# Vertical_Breakout_Module.net
KiCad netlist of a schematic drawn in EAGLE
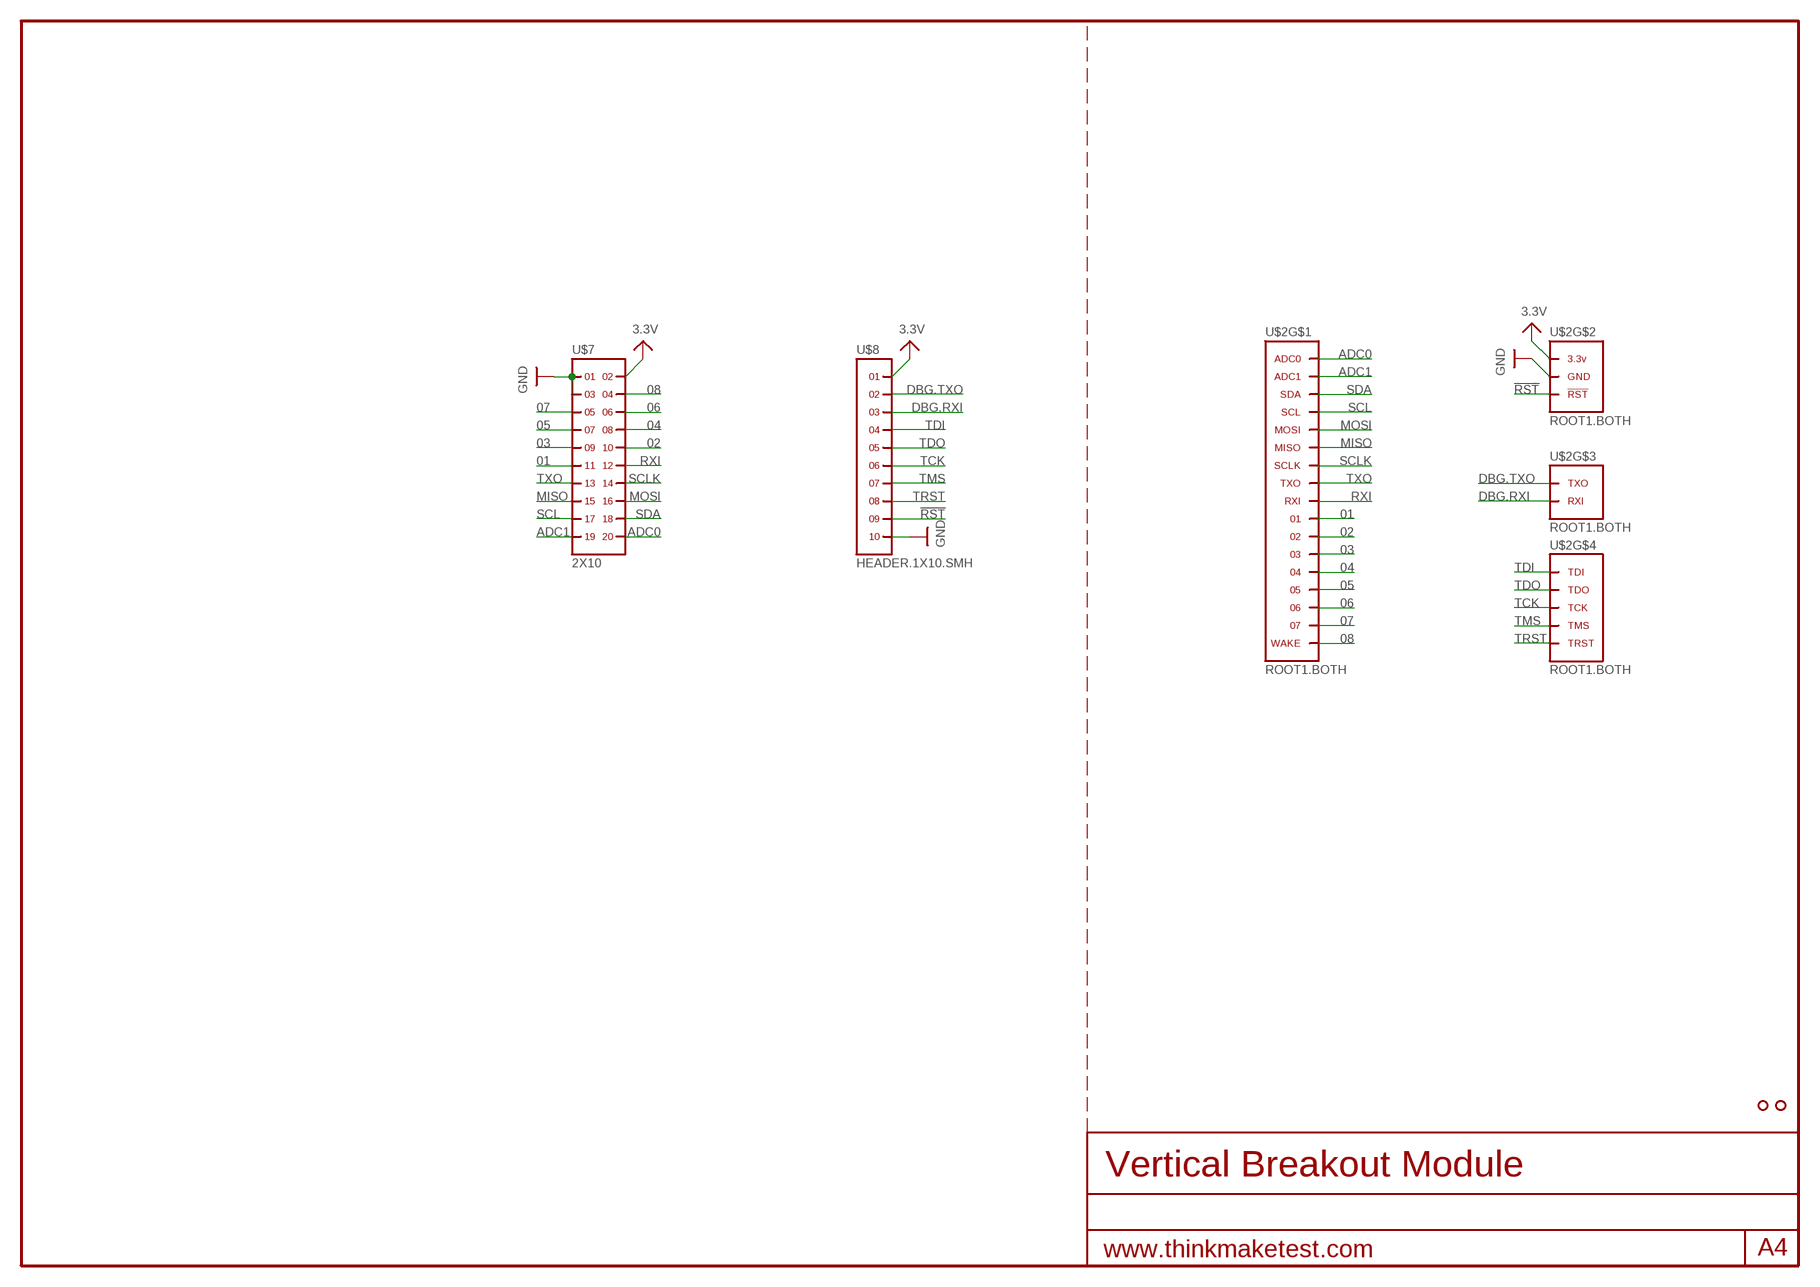
[diagram p0: schematic, sheet 1]

(export (version "E")
  (design (tool "Eeschema 10.0.6"))
  (components
    (comp (ref "U$2")
      (value "ROOT1.BOTH")
      (footprint "eagle-import:ROOT1.BOTH")
      (libsource (lib "eagle-import") (part "ROOT1.BOTH"))
    )
    (comp (ref "U$3")
      (value "HOLE.#2")
      (footprint "eagle-import:#2")
      (libsource (lib "eagle-import") (part "HOLE.#2"))
    )
    (comp (ref "U$4")
      (value "HOLE.#2")
      (footprint "eagle-import:#2")
      (libsource (lib "eagle-import") (part "HOLE.#2"))
    )
    (comp (ref "U$7")
      (value "2X10")
      (footprint "eagle-import:2X10")
      (libsource (lib "eagle-import") (part "2X10"))
    )
    (comp (ref "U$8")
      (value "HEADER.1X10.SMH")
      (footprint "eagle-import:SMH-110-XX-X-S")
      (libsource (lib "eagle-import") (part "HEADER.1X10.SMH"))
    )
  )
  (nets
    (net (code "1") (name "/01") (class "Default")
      (node (ref "U$2") (pin "01") (pinfunction "01_01") (pintype "bidirectional"))
      (node (ref "U$2") (pin "01@1") (pinfunction "01_01@1") (pintype "bidirectional"))
      (node (ref "U$2") (pin "01@VIA") (pinfunction "01_01@VIA") (pintype "bidirectional"))
      (node (ref "U$7") (pin "11") (pinfunction "11_11") (pintype "bidirectional"))
    )
    (net (code "2") (name "/02") (class "Default")
      (node (ref "U$2") (pin "02") (pinfunction "02_02") (pintype "bidirectional"))
      (node (ref "U$2") (pin "02@1") (pinfunction "02_02@1") (pintype "bidirectional"))
      (node (ref "U$2") (pin "02@VIA") (pinfunction "02_02@VIA") (pintype "bidirectional"))
      (node (ref "U$7") (pin "10") (pinfunction "10_10") (pintype "bidirectional"))
    )
    (net (code "3") (name "/03") (class "Default")
      (node (ref "U$2") (pin "03") (pinfunction "03_03") (pintype "bidirectional"))
      (node (ref "U$2") (pin "03@1") (pinfunction "03_03@1") (pintype "bidirectional"))
      (node (ref "U$2") (pin "03@VIA") (pinfunction "03_03@VIA") (pintype "bidirectional"))
      (node (ref "U$7") (pin "9") (pinfunction "9_9") (pintype "bidirectional"))
    )
    (net (code "4") (name "/04") (class "Default")
      (node (ref "U$2") (pin "04") (pinfunction "04_04") (pintype "bidirectional"))
      (node (ref "U$2") (pin "04@1") (pinfunction "04_04@1") (pintype "bidirectional"))
      (node (ref "U$2") (pin "04@VIA") (pinfunction "04_04@VIA") (pintype "bidirectional"))
      (node (ref "U$7") (pin "8") (pinfunction "8_8") (pintype "bidirectional"))
    )
    (net (code "5") (name "/05") (class "Default")
      (node (ref "U$2") (pin "05") (pinfunction "05_05") (pintype "bidirectional"))
      (node (ref "U$2") (pin "05@1") (pinfunction "05_05@1") (pintype "bidirectional"))
      (node (ref "U$2") (pin "05@VIA") (pinfunction "05_05@VIA") (pintype "bidirectional"))
      (node (ref "U$7") (pin "7") (pinfunction "7_7") (pintype "bidirectional"))
    )
    (net (code "6") (name "/06") (class "Default")
      (node (ref "U$2") (pin "06") (pinfunction "06_06") (pintype "bidirectional"))
      (node (ref "U$2") (pin "06@1") (pinfunction "06_06@1") (pintype "bidirectional"))
      (node (ref "U$2") (pin "06@VIA") (pinfunction "06_06@VIA") (pintype "bidirectional"))
      (node (ref "U$7") (pin "6") (pinfunction "6_6") (pintype "bidirectional"))
    )
    (net (code "7") (name "/07") (class "Default")
      (node (ref "U$2") (pin "07") (pinfunction "07_07") (pintype "bidirectional"))
      (node (ref "U$2") (pin "07@1") (pinfunction "07_07@1") (pintype "bidirectional"))
      (node (ref "U$2") (pin "07@VIA") (pinfunction "07_07@VIA") (pintype "bidirectional"))
      (node (ref "U$7") (pin "5") (pinfunction "5_5") (pintype "bidirectional"))
    )
    (net (code "8") (name "/08") (class "Default")
      (node (ref "U$2") (pin "WAKE") (pinfunction "WAKE_WAKE") (pintype "bidirectional"))
      (node (ref "U$2") (pin "WAKE@1") (pinfunction "WAKE_WAKE@1") (pintype "bidirectional"))
      (node (ref "U$2") (pin "WAKE@VIA") (pinfunction "WAKE_WAKE@VIA") (pintype "bidirectional"))
      (node (ref "U$7") (pin "4") (pinfunction "4_4") (pintype "bidirectional"))
    )
    (net (code "9") (name "/ADC0") (class "Default")
      (node (ref "U$2") (pin "ADC0") (pinfunction "ADC0_ADC0") (pintype "bidirectional"))
      (node (ref "U$2") (pin "ADC0@1") (pinfunction "ADC0_ADC0@1") (pintype "bidirectional"))
      (node (ref "U$2") (pin "ADC0@VIA") (pinfunction "ADC0_ADC0@VIA") (pintype "bidirectional"))
      (node (ref "U$7") (pin "20") (pinfunction "20_20") (pintype "bidirectional"))
    )
    (net (code "10") (name "/ADC1") (class "Default")
      (node (ref "U$2") (pin "ADC1") (pinfunction "ADC1_ADC1") (pintype "bidirectional"))
      (node (ref "U$2") (pin "ADC1@1") (pinfunction "ADC1_ADC1@1") (pintype "bidirectional"))
      (node (ref "U$2") (pin "ADC1@VIA") (pinfunction "ADC1_ADC1@VIA") (pintype "bidirectional"))
      (node (ref "U$7") (pin "19") (pinfunction "19_19") (pintype "bidirectional"))
    )
    (net (code "11") (name "/DBG.RXI") (class "Default")
      (node (ref "U$2") (pin "RXI.DBG") (pinfunction "RXI_RXI.DBG") (pintype "bidirectional"))
      (node (ref "U$2") (pin "RXI.DBG@1") (pinfunction "RXI_RXI.DBG@1") (pintype "bidirectional"))
      (node (ref "U$2") (pin "RXI.DBG@VIA") (pinfunction "RXI_RXI.DBG@VIA") (pintype "bidirectional"))
      (node (ref "U$8") (pin "3") (pinfunction "3_3") (pintype "bidirectional"))
    )
    (net (code "12") (name "/DBG.TXO") (class "Default")
      (node (ref "U$2") (pin "TXO.DBG") (pinfunction "TXO_TXO.DBG") (pintype "bidirectional"))
      (node (ref "U$2") (pin "TXO.DBG@1") (pinfunction "TXO_TXO.DBG@1") (pintype "bidirectional"))
      (node (ref "U$2") (pin "TXO.DBG@VIA") (pinfunction "TXO_TXO.DBG@VIA") (pintype "bidirectional"))
      (node (ref "U$8") (pin "2") (pinfunction "2_2") (pintype "bidirectional"))
    )
    (net (code "13") (name "/MISO") (class "Default")
      (node (ref "U$2") (pin "MISO") (pinfunction "MISO_MISO") (pintype "bidirectional"))
      (node (ref "U$2") (pin "MISO@1") (pinfunction "MISO_MISO@1") (pintype "bidirectional"))
      (node (ref "U$2") (pin "MISO@VIA") (pinfunction "MISO_MISO@VIA") (pintype "bidirectional"))
      (node (ref "U$7") (pin "15") (pinfunction "15_15") (pintype "bidirectional"))
    )
    (net (code "14") (name "/MOSI") (class "Default")
      (node (ref "U$2") (pin "MOSI") (pinfunction "MOSI_MOSI") (pintype "bidirectional"))
      (node (ref "U$2") (pin "MOSI@1") (pinfunction "MOSI_MOSI@1") (pintype "bidirectional"))
      (node (ref "U$2") (pin "MOSI@VIA") (pinfunction "MOSI_MOSI@VIA") (pintype "bidirectional"))
      (node (ref "U$7") (pin "16") (pinfunction "16_16") (pintype "bidirectional"))
    )
    (net (code "15") (name "/RXI") (class "Default")
      (node (ref "U$2") (pin "RXI") (pinfunction "RXI_RXI") (pintype "bidirectional"))
      (node (ref "U$2") (pin "RXI@1") (pinfunction "RXI_RXI@1") (pintype "bidirectional"))
      (node (ref "U$2") (pin "RXI@VIA") (pinfunction "RXI_RXI@VIA") (pintype "bidirectional"))
      (node (ref "U$7") (pin "12") (pinfunction "12_12") (pintype "bidirectional"))
    )
    (net (code "16") (name "/SCL") (class "Default")
      (node (ref "U$2") (pin "SCL") (pinfunction "SCL_SCL") (pintype "bidirectional"))
      (node (ref "U$2") (pin "SCL@1") (pinfunction "SCL_SCL@1") (pintype "bidirectional"))
      (node (ref "U$2") (pin "SCL@VIA") (pinfunction "SCL_SCL@VIA") (pintype "bidirectional"))
      (node (ref "U$7") (pin "17") (pinfunction "17_17") (pintype "bidirectional"))
    )
    (net (code "17") (name "/SCLK") (class "Default")
      (node (ref "U$2") (pin "SCLK") (pinfunction "SCLK_SCLK") (pintype "bidirectional"))
      (node (ref "U$2") (pin "SCLK@1") (pinfunction "SCLK_SCLK@1") (pintype "bidirectional"))
      (node (ref "U$2") (pin "SCLK@VIA") (pinfunction "SCLK_SCLK@VIA") (pintype "bidirectional"))
      (node (ref "U$7") (pin "14") (pinfunction "14_14") (pintype "bidirectional"))
    )
    (net (code "18") (name "/SDA") (class "Default")
      (node (ref "U$2") (pin "SDA") (pinfunction "SDA_SDA") (pintype "bidirectional"))
      (node (ref "U$2") (pin "SDA@1") (pinfunction "SDA_SDA@1") (pintype "bidirectional"))
      (node (ref "U$2") (pin "SDA@VIA") (pinfunction "SDA_SDA@VIA") (pintype "bidirectional"))
      (node (ref "U$7") (pin "18") (pinfunction "18_18") (pintype "bidirectional"))
    )
    (net (code "19") (name "/TCK") (class "Default")
      (node (ref "U$2") (pin "TCK") (pinfunction "TCK_TCK") (pintype "bidirectional"))
      (node (ref "U$2") (pin "TCK@1") (pinfunction "TCK_TCK@1") (pintype "bidirectional"))
      (node (ref "U$2") (pin "TCK@VIA") (pinfunction "TCK_TCK@VIA") (pintype "bidirectional"))
      (node (ref "U$8") (pin "6") (pinfunction "6_6") (pintype "bidirectional"))
    )
    (net (code "20") (name "/TDI") (class "Default")
      (node (ref "U$2") (pin "TDI") (pinfunction "TDI_TDI") (pintype "bidirectional"))
      (node (ref "U$2") (pin "TDI@1") (pinfunction "TDI_TDI@1") (pintype "bidirectional"))
      (node (ref "U$2") (pin "TDI@VIA") (pinfunction "TDI_TDI@VIA") (pintype "bidirectional"))
      (node (ref "U$8") (pin "4") (pinfunction "4_4") (pintype "bidirectional"))
    )
    (net (code "21") (name "/TDO") (class "Default")
      (node (ref "U$2") (pin "TDO") (pinfunction "TDO_TDO") (pintype "bidirectional"))
      (node (ref "U$2") (pin "TDO@1") (pinfunction "TDO_TDO@1") (pintype "bidirectional"))
      (node (ref "U$2") (pin "TDO@VIA") (pinfunction "TDO_TDO@VIA") (pintype "bidirectional"))
      (node (ref "U$8") (pin "5") (pinfunction "5_5") (pintype "bidirectional"))
    )
    (net (code "22") (name "/TMS") (class "Default")
      (node (ref "U$2") (pin "TMS") (pinfunction "TMS_TMS") (pintype "bidirectional"))
      (node (ref "U$2") (pin "TMS@1") (pinfunction "TMS_TMS@1") (pintype "bidirectional"))
      (node (ref "U$2") (pin "TMS@VIA") (pinfunction "TMS_TMS@VIA") (pintype "bidirectional"))
      (node (ref "U$8") (pin "7") (pinfunction "7_7") (pintype "bidirectional"))
    )
    (net (code "23") (name "/TRST") (class "Default")
      (node (ref "U$2") (pin "TRST") (pinfunction "TRST_TRST") (pintype "bidirectional"))
      (node (ref "U$2") (pin "TRST@1") (pinfunction "TRST_TRST@1") (pintype "bidirectional"))
      (node (ref "U$2") (pin "TRST@VIA") (pinfunction "TRST_TRST@VIA") (pintype "bidirectional"))
      (node (ref "U$8") (pin "8") (pinfunction "8_8") (pintype "bidirectional"))
    )
    (net (code "24") (name "/TXO") (class "Default")
      (node (ref "U$2") (pin "TXO") (pinfunction "TXO_TXO") (pintype "bidirectional"))
      (node (ref "U$2") (pin "TXO@1") (pinfunction "TXO_TXO@1") (pintype "bidirectional"))
      (node (ref "U$2") (pin "TXO@VIA") (pinfunction "TXO_TXO@VIA") (pintype "bidirectional"))
      (node (ref "U$7") (pin "13") (pinfunction "13_13") (pintype "bidirectional"))
    )
    (net (code "25") (name "/~{RST}") (class "Default")
      (node (ref "U$2") (pin "RST") (pinfunction "~{RST}_RST") (pintype "bidirectional"))
      (node (ref "U$2") (pin "RST@1") (pinfunction "~{RST}_RST@1") (pintype "bidirectional"))
      (node (ref "U$2") (pin "RST@VIA") (pinfunction "~{RST}_RST@VIA") (pintype "bidirectional"))
      (node (ref "U$8") (pin "9") (pinfunction "9_9") (pintype "bidirectional"))
    )
    (net (code "26") (name "3.3V") (class "Default")
      (node (ref "U$2") (pin "3.3V@1") (pinfunction "3.3V_3.3V@1") (pintype "bidirectional"))
      (node (ref "U$2") (pin "3.3V@10") (pinfunction "3.3V_3.3V@10") (pintype "bidirectional"))
      (node (ref "U$2") (pin "3.3V@11") (pinfunction "3.3V_3.3V@11") (pintype "bidirectional"))
      (node (ref "U$2") (pin "3.3V@12") (pinfunction "3.3V_3.3V@12") (pintype "bidirectional"))
      (node (ref "U$2") (pin "3.3V@13") (pinfunction "3.3V_3.3V@13") (pintype "bidirectional"))
      (node (ref "U$2") (pin "3.3V@14") (pinfunction "3.3V_3.3V@14") (pintype "bidirectional"))
      (node (ref "U$2") (pin "3.3V@15") (pinfunction "3.3V_3.3V@15") (pintype "bidirectional"))
      (node (ref "U$2") (pin "3.3V@16") (pinfunction "3.3V_3.3V@16") (pintype "bidirectional"))
      (node (ref "U$2") (pin "3.3V@17") (pinfunction "3.3V_3.3V@17") (pintype "bidirectional"))
      (node (ref "U$2") (pin "3.3V@18") (pinfunction "3.3V_3.3V@18") (pintype "bidirectional"))
      (node (ref "U$2") (pin "3.3V@19") (pinfunction "3.3V_3.3V@19") (pintype "bidirectional"))
      (node (ref "U$2") (pin "3.3V@2") (pinfunction "3.3V_3.3V@2") (pintype "bidirectional"))
      (node (ref "U$2") (pin "3.3V@20") (pinfunction "3.3V_3.3V@20") (pintype "bidirectional"))
      (node (ref "U$2") (pin "3.3V@21") (pinfunction "3.3V_3.3V@21") (pintype "bidirectional"))
      (node (ref "U$2") (pin "3.3V@22") (pinfunction "3.3V_3.3V@22") (pintype "bidirectional"))
      (node (ref "U$2") (pin "3.3V@23") (pinfunction "3.3V_3.3V@23") (pintype "bidirectional"))
      (node (ref "U$2") (pin "3.3V@24") (pinfunction "3.3V_3.3V@24") (pintype "bidirectional"))
      (node (ref "U$2") (pin "3.3V@3") (pinfunction "3.3V_3.3V@3") (pintype "bidirectional"))
      (node (ref "U$2") (pin "3.3V@4") (pinfunction "3.3V_3.3V@4") (pintype "bidirectional"))
      (node (ref "U$2") (pin "3.3V@5") (pinfunction "3.3V_3.3V@5") (pintype "bidirectional"))
      (node (ref "U$2") (pin "3.3V@6") (pinfunction "3.3V_3.3V@6") (pintype "bidirectional"))
      (node (ref "U$2") (pin "3.3V@7") (pinfunction "3.3V_3.3V@7") (pintype "bidirectional"))
      (node (ref "U$2") (pin "3.3V@8") (pinfunction "3.3V_3.3V@8") (pintype "bidirectional"))
      (node (ref "U$2") (pin "3.3V@9") (pinfunction "3.3V_3.3V@9") (pintype "bidirectional"))
      (node (ref "U$2") (pin "3.3V@VIA") (pinfunction "3.3V_3.3V@VIA") (pintype "bidirectional"))
      (node (ref "U$7") (pin "2") (pinfunction "2_2") (pintype "bidirectional"))
      (node (ref "U$8") (pin "1") (pinfunction "1_1") (pintype "bidirectional"))
    )
    (net (code "27") (name "GND") (class "Default")
      (node (ref "U$2") (pin "GND@1") (pinfunction "GND_GND@1") (pintype "bidirectional"))
      (node (ref "U$2") (pin "GND@10") (pinfunction "GND_GND@10") (pintype "bidirectional"))
      (node (ref "U$2") (pin "GND@11") (pinfunction "GND_GND@11") (pintype "bidirectional"))
      (node (ref "U$2") (pin "GND@12") (pinfunction "GND_GND@12") (pintype "bidirectional"))
      (node (ref "U$2") (pin "GND@13") (pinfunction "GND_GND@13") (pintype "bidirectional"))
      (node (ref "U$2") (pin "GND@14") (pinfunction "GND_GND@14") (pintype "bidirectional"))
      (node (ref "U$2") (pin "GND@15") (pinfunction "GND_GND@15") (pintype "bidirectional"))
      (node (ref "U$2") (pin "GND@16") (pinfunction "GND_GND@16") (pintype "bidirectional"))
      (node (ref "U$2") (pin "GND@17") (pinfunction "GND_GND@17") (pintype "bidirectional"))
      (node (ref "U$2") (pin "GND@18") (pinfunction "GND_GND@18") (pintype "bidirectional"))
      (node (ref "U$2") (pin "GND@19") (pinfunction "GND_GND@19") (pintype "bidirectional"))
      (node (ref "U$2") (pin "GND@2") (pinfunction "GND_GND@2") (pintype "bidirectional"))
      (node (ref "U$2") (pin "GND@20") (pinfunction "GND_GND@20") (pintype "bidirectional"))
      (node (ref "U$2") (pin "GND@21") (pinfunction "GND_GND@21") (pintype "bidirectional"))
      (node (ref "U$2") (pin "GND@22") (pinfunction "GND_GND@22") (pintype "bidirectional"))
      (node (ref "U$2") (pin "GND@23") (pinfunction "GND_GND@23") (pintype "bidirectional"))
      (node (ref "U$2") (pin "GND@24") (pinfunction "GND_GND@24") (pintype "bidirectional"))
      (node (ref "U$2") (pin "GND@25") (pinfunction "GND_GND@25") (pintype "bidirectional"))
      (node (ref "U$2") (pin "GND@26") (pinfunction "GND_GND@26") (pintype "bidirectional"))
      (node (ref "U$2") (pin "GND@3") (pinfunction "GND_GND@3") (pintype "bidirectional"))
      (node (ref "U$2") (pin "GND@4") (pinfunction "GND_GND@4") (pintype "bidirectional"))
      (node (ref "U$2") (pin "GND@5") (pinfunction "GND_GND@5") (pintype "bidirectional"))
      (node (ref "U$2") (pin "GND@6") (pinfunction "GND_GND@6") (pintype "bidirectional"))
      (node (ref "U$2") (pin "GND@7") (pinfunction "GND_GND@7") (pintype "bidirectional"))
      (node (ref "U$2") (pin "GND@8") (pinfunction "GND_GND@8") (pintype "bidirectional"))
      (node (ref "U$2") (pin "GND@9") (pinfunction "GND_GND@9") (pintype "bidirectional"))
      (node (ref "U$2") (pin "GND@VIA") (pinfunction "GND_GND@VIA") (pintype "bidirectional"))
      (node (ref "U$7") (pin "1") (pinfunction "1_1") (pintype "bidirectional"))
      (node (ref "U$7") (pin "3") (pinfunction "3_3") (pintype "bidirectional"))
      (node (ref "U$8") (pin "10") (pinfunction "10_10") (pintype "bidirectional"))
    )
  )
)
